# SDCard.net
KiCad netlist of a schematic drawn in Altium Designer
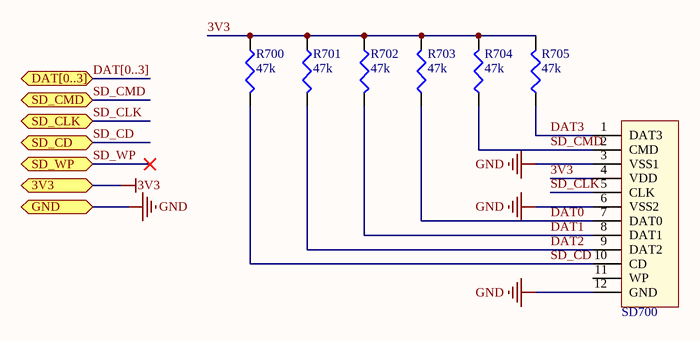
[diagram p0: SDCard.SchDoc]

(export (version "E")
  (design (tool "Eeschema 10.0.6"))
  (components
    (comp (ref "R700")
      (value "47k")
      (footprint "SMD0603")
      (description "Resistor")
      (fields (field (name "Comment") "Res"))
      (libsource (lib "Components") (part "Resistor"))
    )
    (comp (ref "R701")
      (value "47k")
      (footprint "SMD0603")
      (description "Resistor")
      (fields (field (name "Comment") "Res"))
      (libsource (lib "Components") (part "Resistor"))
    )
    (comp (ref "R702")
      (value "47k")
      (footprint "SMD0603")
      (description "Resistor")
      (fields (field (name "Comment") "Res"))
      (libsource (lib "Components") (part "Resistor"))
    )
    (comp (ref "R703")
      (value "47k")
      (footprint "SMD0603")
      (description "Resistor")
      (fields (field (name "Comment") "Res"))
      (libsource (lib "Components") (part "Resistor"))
    )
    (comp (ref "R704")
      (value "47k")
      (footprint "SMD0603")
      (description "Resistor")
      (fields (field (name "Comment") "Res"))
      (libsource (lib "Components") (part "Resistor"))
    )
    (comp (ref "R705")
      (value "47k")
      (footprint "SMD0603")
      (description "Resistor")
      (fields (field (name "Comment") "Res"))
      (libsource (lib "Components") (part "Resistor"))
    )
    (comp (ref "SD700")
      (value "SD Card Slot")
      (footprint "SDCARD-AMP")
      (description "SD Card Connector (Amphenol)")
      (libsource (lib "Components") (part "SD Card Slot"))
    )
  )
  (nets
    (net (code "1") (name "/DAT0") (class "Default")
      (node (ref "R703") (pin "1") (pinfunction "1_1") (pintype "passive"))
      (node (ref "SD700") (pin "7") (pinfunction "DAT0_7") (pintype "passive"))
    )
    (net (code "2") (name "/DAT1") (class "Default")
      (node (ref "R702") (pin "2") (pinfunction "2_2") (pintype "passive"))
      (node (ref "SD700") (pin "8") (pinfunction "DAT1_8") (pintype "passive"))
    )
    (net (code "3") (name "/DAT2") (class "Default")
      (node (ref "R701") (pin "2") (pinfunction "2_2") (pintype "passive"))
      (node (ref "SD700") (pin "9") (pinfunction "DAT2_9") (pintype "passive"))
    )
    (net (code "4") (name "/DAT3") (class "Default")
      (node (ref "R705") (pin "1") (pinfunction "1_1") (pintype "passive"))
      (node (ref "SD700") (pin "1") (pinfunction "DAT3_1") (pintype "passive"))
    )
    (net (code "6") (name "/SD_CD") (class "Default")
      (node (ref "R700") (pin "2") (pinfunction "2_2") (pintype "passive"))
      (node (ref "SD700") (pin "10") (pinfunction "CD_10") (pintype "passive"))
    )
    (net (code "7") (name "/SD_CLK") (class "Default")
      (node (ref "SD700") (pin "5") (pinfunction "CLK_5") (pintype "passive"))
    )
    (net (code "8") (name "/SD_CMD") (class "Default")
      (node (ref "R704") (pin "1") (pinfunction "1_1") (pintype "passive"))
      (node (ref "SD700") (pin "2") (pinfunction "CMD_2") (pintype "passive"))
    )
    (net (code "10") (name "3V3") (class "Default")
      (node (ref "R700") (pin "1") (pinfunction "1_1") (pintype "passive"))
      (node (ref "R701") (pin "1") (pinfunction "1_1") (pintype "passive"))
      (node (ref "R702") (pin "1") (pinfunction "1_1") (pintype "passive"))
      (node (ref "R703") (pin "2") (pinfunction "2_2") (pintype "passive"))
      (node (ref "R704") (pin "2") (pinfunction "2_2") (pintype "passive"))
      (node (ref "R705") (pin "2") (pinfunction "2_2") (pintype "passive"))
      (node (ref "SD700") (pin "4") (pinfunction "VDD_4") (pintype "passive"))
    )
    (net (code "11") (name "GND") (class "Default")
      (node (ref "SD700") (pin "12") (pinfunction "GND_12") (pintype "passive"))
      (node (ref "SD700") (pin "3") (pinfunction "VSS1_3") (pintype "passive"))
      (node (ref "SD700") (pin "6") (pinfunction "VSS2_6") (pintype "passive"))
    )
    (net (code "12") (name "unconnected-(SD700-WP-Pad11)") (class "Default")
      (node (ref "SD700") (pin "11") (pinfunction "WP_11") (pintype "passive"))
    )
  )
)
